# EndSwitch_OptoBoard.net
KiCad netlist of a schematic drawn in EAGLE
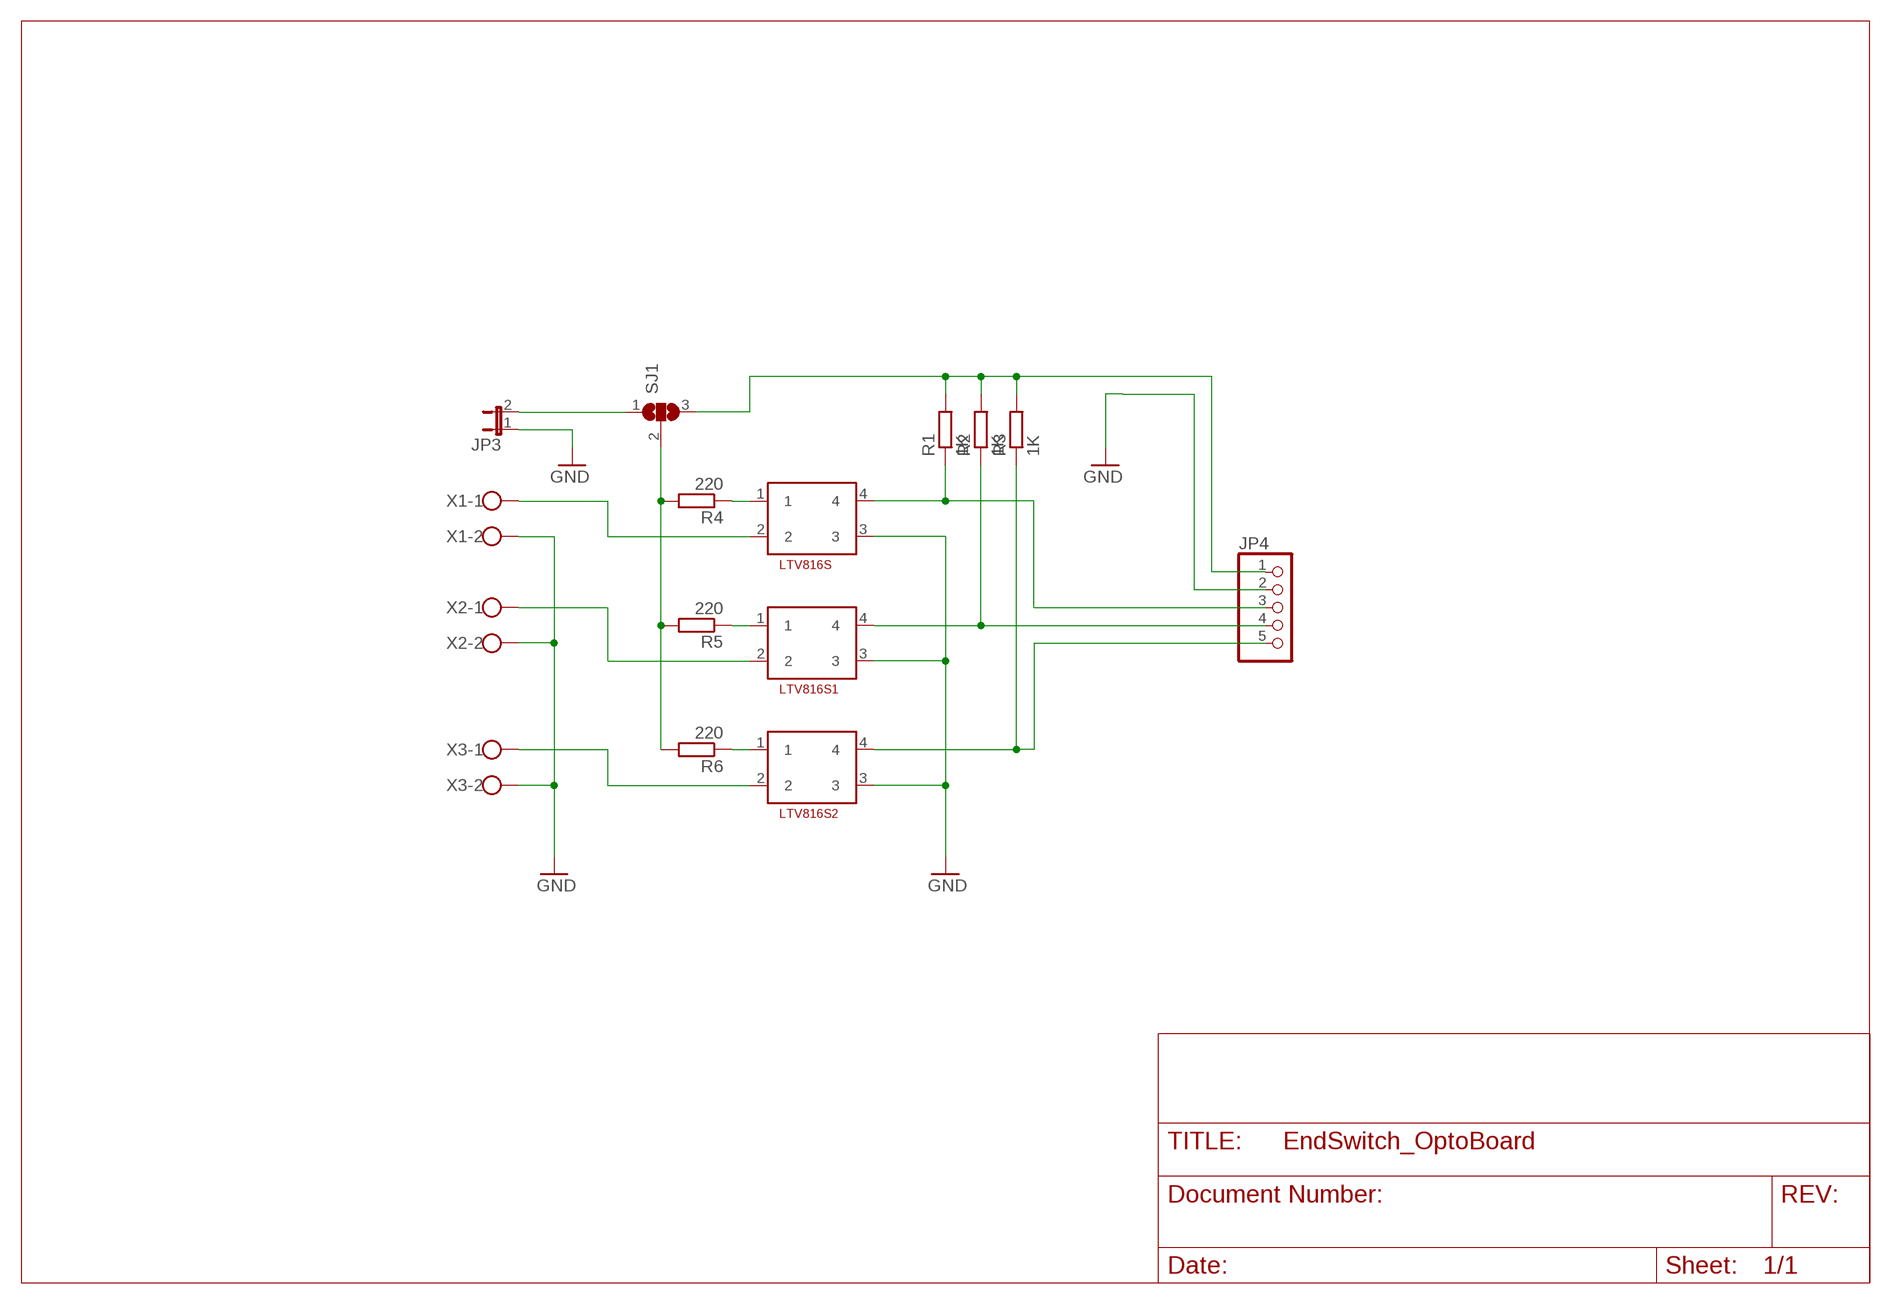
[diagram p0: schematic, sheet 1]

(export (version "E")
  (design (tool "Eeschema 10.0.6"))
  (components
    (comp (ref "JP3")
      (value "JP1E")
      (footprint "eagle-import:JP1")
      (libsource (lib "eagle-import") (part "JP1E"))
    )
    (comp (ref "JP4")
      (value "PINHD-1X5")
      (footprint "eagle-import:1X05")
      (libsource (lib "eagle-import") (part "PINHD-1X5"))
    )
    (comp (ref "LTV816S")
      (value "LTV816S")
      (footprint "eagle-import:LTV816S")
      (libsource (lib "eagle-import") (part "LTV816S"))
    )
    (comp (ref "LTV816S1")
      (value "LTV816S")
      (footprint "eagle-import:LTV816S")
      (libsource (lib "eagle-import") (part "LTV816S"))
    )
    (comp (ref "LTV816S2")
      (value "LTV816S")
      (footprint "eagle-import:LTV816S")
      (libsource (lib "eagle-import") (part "LTV816S"))
    )
    (comp (ref "R1")
      (value "1K")
      (footprint "eagle-import:R0603")
      (libsource (lib "eagle-import") (part "R-EU_R0603"))
    )
    (comp (ref "R2")
      (value "1K")
      (footprint "eagle-import:R0603")
      (libsource (lib "eagle-import") (part "R-EU_R0603"))
    )
    (comp (ref "R3")
      (value "1K")
      (footprint "eagle-import:R0603")
      (libsource (lib "eagle-import") (part "R-EU_R0603"))
    )
    (comp (ref "R4")
      (value "220")
      (footprint "eagle-import:R0603")
      (libsource (lib "eagle-import") (part "R-EU_R0603"))
    )
    (comp (ref "R5")
      (value "220")
      (footprint "eagle-import:R0603")
      (libsource (lib "eagle-import") (part "R-EU_R0603"))
    )
    (comp (ref "R6")
      (value "220")
      (footprint "eagle-import:R0603")
      (libsource (lib "eagle-import") (part "R-EU_R0603"))
    )
    (comp (ref "SJ1")
      (value "SJ2W")
      (footprint "eagle-import:SJ_2")
      (libsource (lib "eagle-import") (part "SJ2W"))
    )
    (comp (ref "X1")
      (value "W237-102")
      (footprint "eagle-import:W237-102")
      (fields (field (name "MPN") "237-102"))
      (libsource (lib "eagle-import") (part "W237-102"))
    )
    (comp (ref "X2")
      (value "W237-102")
      (footprint "eagle-import:W237-102")
      (fields (field (name "MPN") "237-102"))
      (libsource (lib "eagle-import") (part "W237-102"))
    )
    (comp (ref "X3")
      (value "W237-102")
      (footprint "eagle-import:W237-102")
      (fields (field (name "MPN") "237-102"))
      (libsource (lib "eagle-import") (part "W237-102"))
    )
  )
  (nets
    (net (code "1") (name "GND") (class "Default")
      (node (ref "JP3") (pin "1") (pinfunction "1_1") (pintype "passive"))
      (node (ref "JP4") (pin "2") (pinfunction "2_2") (pintype "passive"))
      (node (ref "LTV816S") (pin "3") (pinfunction "3_3") (pintype "output"))
      (node (ref "LTV816S1") (pin "3") (pinfunction "3_3") (pintype "output"))
      (node (ref "LTV816S2") (pin "3") (pinfunction "3_3") (pintype "output"))
      (node (ref "X1") (pin "2") (pinfunction "KL_2") (pintype "passive"))
      (node (ref "X2") (pin "2") (pinfunction "KL_2") (pintype "passive"))
      (node (ref "X3") (pin "2") (pinfunction "KL_2") (pintype "passive"))
    )
    (net (code "2") (name "Net-(JP3-Pad2)") (class "Default")
      (node (ref "JP3") (pin "2") (pinfunction "2_2") (pintype "passive"))
      (node (ref "SJ1") (pin "1") (pinfunction "1_1") (pintype "passive"))
    )
    (net (code "3") (name "Net-(JP4-Pad1)") (class "Default")
      (node (ref "JP4") (pin "1") (pinfunction "1_1") (pintype "passive"))
      (node (ref "R1") (pin "2") (pinfunction "2_2") (pintype "passive"))
      (node (ref "R2") (pin "2") (pinfunction "2_2") (pintype "passive"))
      (node (ref "R3") (pin "2") (pinfunction "2_2") (pintype "passive"))
      (node (ref "SJ1") (pin "3") (pinfunction "3_3") (pintype "passive"))
    )
    (net (code "4") (name "Net-(JP4-Pad3)") (class "Default")
      (node (ref "JP4") (pin "3") (pinfunction "3_3") (pintype "passive"))
      (node (ref "LTV816S") (pin "4") (pinfunction "4_4") (pintype "input"))
      (node (ref "R1") (pin "1") (pinfunction "1_1") (pintype "passive"))
    )
    (net (code "5") (name "Net-(JP4-Pad4)") (class "Default")
      (node (ref "JP4") (pin "4") (pinfunction "4_4") (pintype "passive"))
      (node (ref "LTV816S1") (pin "4") (pinfunction "4_4") (pintype "input"))
      (node (ref "R2") (pin "1") (pinfunction "1_1") (pintype "passive"))
    )
    (net (code "6") (name "Net-(JP4-Pad5)") (class "Default")
      (node (ref "JP4") (pin "5") (pinfunction "5_5") (pintype "passive"))
      (node (ref "LTV816S2") (pin "4") (pinfunction "4_4") (pintype "input"))
      (node (ref "R3") (pin "1") (pinfunction "1_1") (pintype "passive"))
    )
    (net (code "7") (name "Net-(LTV816S-Pad1)") (class "Default")
      (node (ref "LTV816S") (pin "1") (pinfunction "1_1") (pintype "input"))
      (node (ref "R4") (pin "1") (pinfunction "1_1") (pintype "passive"))
    )
    (net (code "8") (name "Net-(LTV816S1-Pad1)") (class "Default")
      (node (ref "LTV816S1") (pin "1") (pinfunction "1_1") (pintype "input"))
      (node (ref "R5") (pin "1") (pinfunction "1_1") (pintype "passive"))
    )
    (net (code "9") (name "Net-(LTV816S2-Pad1)") (class "Default")
      (node (ref "LTV816S2") (pin "1") (pinfunction "1_1") (pintype "input"))
      (node (ref "R6") (pin "1") (pinfunction "1_1") (pintype "passive"))
    )
    (net (code "10") (name "Net-(R4-Pad2)") (class "Default")
      (node (ref "R4") (pin "2") (pinfunction "2_2") (pintype "passive"))
      (node (ref "R5") (pin "2") (pinfunction "2_2") (pintype "passive"))
      (node (ref "R6") (pin "2") (pinfunction "2_2") (pintype "passive"))
      (node (ref "SJ1") (pin "2") (pinfunction "2_2") (pintype "passive"))
    )
    (net (code "11") (name "Net-(X1A-KL)") (class "Default")
      (node (ref "LTV816S") (pin "2") (pinfunction "2_2") (pintype "output"))
      (node (ref "X1") (pin "1") (pinfunction "KL_1") (pintype "passive"))
    )
    (net (code "12") (name "Net-(X2A-KL)") (class "Default")
      (node (ref "LTV816S1") (pin "2") (pinfunction "2_2") (pintype "output"))
      (node (ref "X2") (pin "1") (pinfunction "KL_1") (pintype "passive"))
    )
    (net (code "13") (name "Net-(X3A-KL)") (class "Default")
      (node (ref "LTV816S2") (pin "2") (pinfunction "2_2") (pintype "output"))
      (node (ref "X3") (pin "1") (pinfunction "KL_1") (pintype "passive"))
    )
  )
)
